# Boost.net
KiCad netlist of a schematic drawn in Altium Designer
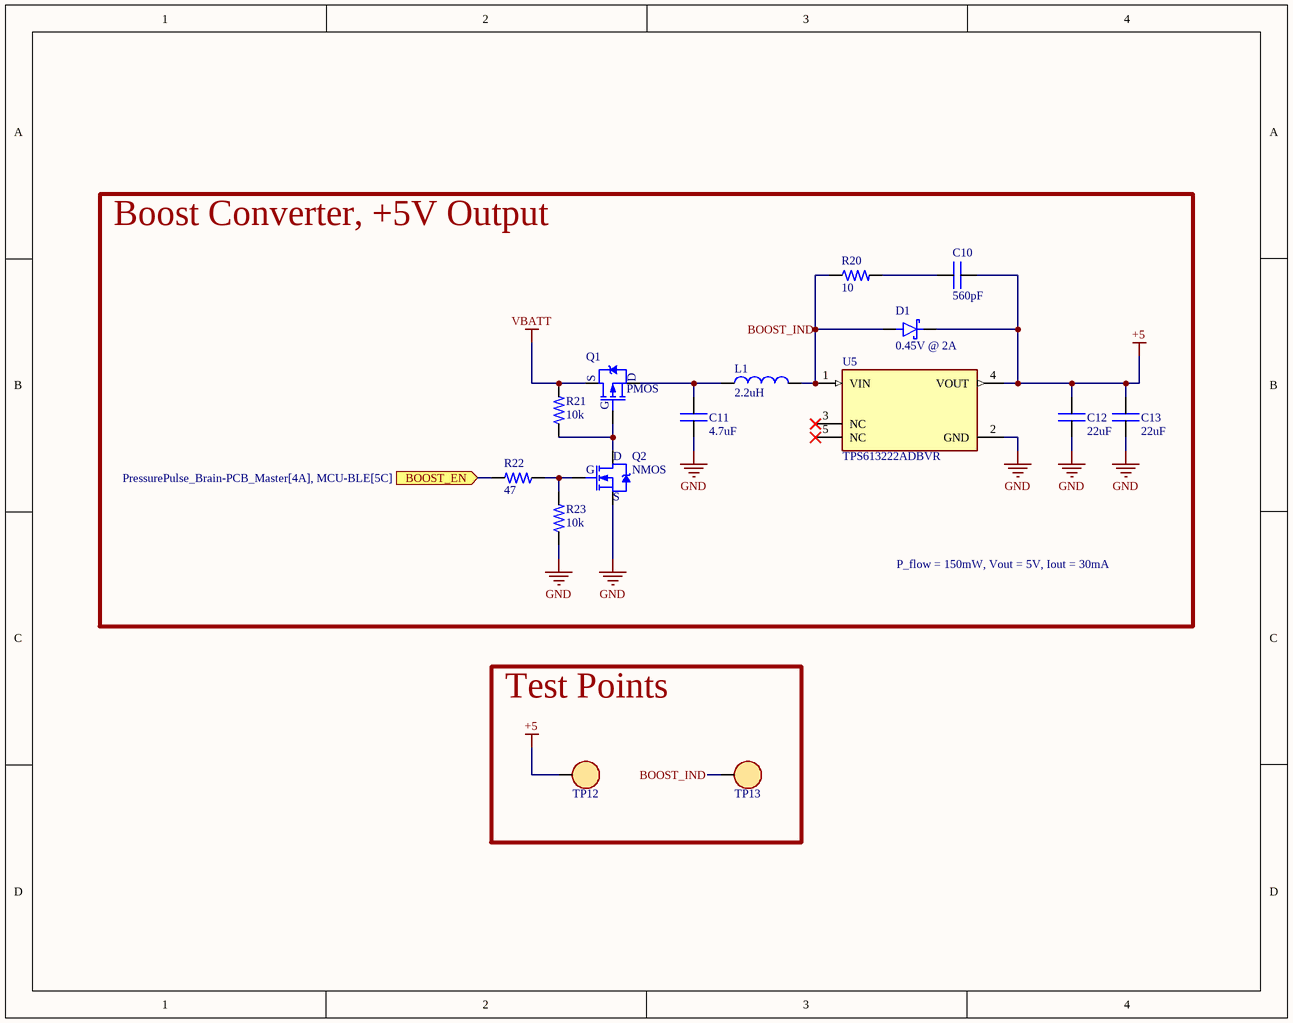
[diagram p0: Boost.SchDoc]

(export (version "E")
  (design (tool "Eeschema 10.0.6"))
  (components
    (comp (ref "C10")
      (value "560pF")
      (footprint "PressurePulse:0805C")
      (description "Capacitor")
      (fields (field (name "Comment") "CAP"))
      (libsource (lib "PressurePulse") (part "CAP"))
    )
    (comp (ref "C11")
      (value "4.7uF")
      (footprint "PressurePulse:0402C")
      (description "Capacitor")
      (fields (field (name "Comment") "CAP"))
      (libsource (lib "PressurePulse") (part "CAP"))
    )
    (comp (ref "C12")
      (value "22uF")
      (footprint "PressurePulse:0805C")
      (description "Capacitor")
      (fields (field (name "MFR") "Samsung Electro-Mechanics") (field (name "Comment") "CAP"))
      (libsource (lib "PressurePulse") (part "CAP"))
    )
    (comp (ref "C13")
      (value "22uF")
      (footprint "PressurePulse:0805C")
      (description "Capacitor")
      (fields (field (name "MFR") "Samsung Electro-Mechanics") (field (name "Comment") "CAP"))
      (libsource (lib "PressurePulse") (part "CAP"))
    )
    (comp (ref "D1")
      (value "0.45V @ 2A")
      (footprint "PressurePulse:SMAF")
      (fields (field (name "MFR") "Shandong Jingdao Microelectronics"))
      (libsource (lib "PressurePulse") (part "SCHOTTKY DIODE"))
    )
    (comp (ref "L1")
      (value "2.2uH")
      (footprint "PressurePulse:0805L")
      (description "INDUCTOR")
      (fields (field (name "MFR") "Sunlord") (field (name "Comment") "IND"))
      (libsource (lib "PressurePulse") (part "IND"))
    )
    (comp (ref "Q1")
      (value "PMOS")
      (footprint "PressurePulse:SOT-23")
      (description "P-Channel MOSFET")
      (fields (field (name "MFR") "Diodes Incorporated"))
      (libsource (lib "PressurePulse") (part "PMOS"))
    )
    (comp (ref "Q2")
      (value "NMOS")
      (footprint "PressurePulse:SOT-23")
      (description "100V 1.6A 1.3W 220mΩ@10V,1.6A N Channel SOT-23  MOSFETs ROHS")
      (fields (field (name "MFR") "Infineon"))
      (libsource (lib "PressurePulse") (part "NMOS"))
    )
    (comp (ref "R20")
      (value "10")
      (footprint "PressurePulse:2512R")
      (description "Resistor")
      (fields (field (name "Comment") "RES"))
      (libsource (lib "PressurePulse") (part "RES"))
    )
    (comp (ref "R21")
      (value "10k")
      (footprint "PressurePulse:0402R")
      (description "Resistor")
      (fields (field (name "Comment") "RES"))
      (libsource (lib "PressurePulse") (part "RES"))
    )
    (comp (ref "R22")
      (value "47")
      (footprint "PressurePulse:0402R")
      (description "Resistor")
      (fields (field (name "Comment") "RES"))
      (libsource (lib "PressurePulse") (part "RES"))
    )
    (comp (ref "R23")
      (value "10k")
      (footprint "PressurePulse:0402R")
      (description "Resistor")
      (fields (field (name "Comment") "RES"))
      (libsource (lib "PressurePulse") (part "RES"))
    )
    (comp (ref "TP12")
      (value "RH-5019")
      (footprint "PressurePulse:TP - RH-5019")
      (fields (field (name "MFR") "ronghe"))
      (libsource (lib "PressurePulse") (part "TEST POINT"))
    )
    (comp (ref "TP13")
      (value "RH-5019")
      (footprint "PressurePulse:TP - RH-5019")
      (fields (field (name "MFR") "ronghe"))
      (libsource (lib "PressurePulse") (part "TEST POINT"))
    )
    (comp (ref "U5")
      (value "TPS613222ADBVR")
      (footprint "PressurePulse:SOT-23-5")
      (description "6-uA Quiescent Current, 1.8-A Switch Current Boost Converter 5-SOT-23 -40 to 85")
      (fields (field (name "MFR") "Texas Instruments"))
      (libsource (lib "PressurePulse") (part "BOOST 3.3V-5V FIXED"))
    )
  )
  (nets
    (net (code "1") (name "+5") (class "Default")
      (node (ref "C10") (pin "2") (pinfunction "2_2") (pintype "passive"))
      (node (ref "C12") (pin "2") (pinfunction "2_2") (pintype "passive"))
      (node (ref "C13") (pin "2") (pinfunction "2_2") (pintype "passive"))
      (node (ref "D1") (pin "K") (pinfunction "K_K") (pintype "passive"))
      (node (ref "TP12") (pin "1") (pinfunction "1_1") (pintype "passive"))
      (node (ref "U5") (pin "4") (pinfunction "VOUT_4") (pintype "output"))
    )
    (net (code "2") (name "/BOOST_EN") (class "Default")
      (node (ref "R22") (pin "2") (pinfunction "2_2") (pintype "passive"))
    )
    (net (code "3") (name "/BOOST_IND") (class "Default")
      (node (ref "D1") (pin "A") (pinfunction "A_A") (pintype "passive"))
      (node (ref "L1") (pin "2") (pinfunction "2_2") (pintype "passive"))
      (node (ref "R20") (pin "1") (pinfunction "1_1") (pintype "passive"))
      (node (ref "TP13") (pin "1") (pinfunction "1_1") (pintype "passive"))
      (node (ref "U5") (pin "1") (pinfunction "VIN_1") (pintype "input"))
    )
    (net (code "4") (name "GND") (class "Default")
      (node (ref "C11") (pin "1") (pinfunction "1_1") (pintype "passive"))
      (node (ref "C12") (pin "1") (pinfunction "1_1") (pintype "passive"))
      (node (ref "C13") (pin "1") (pinfunction "1_1") (pintype "passive"))
      (node (ref "Q2") (pin "S") (pinfunction "S_S") (pintype "passive"))
      (node (ref "R23") (pin "1") (pinfunction "1_1") (pintype "passive"))
      (node (ref "U5") (pin "2") (pinfunction "GND_2") (pintype "power_in"))
    )
    (net (code "5") (name "Net-(C10-Pad1)") (class "Default")
      (node (ref "C10") (pin "1") (pinfunction "1_1") (pintype "passive"))
      (node (ref "R20") (pin "2") (pinfunction "2_2") (pintype "passive"))
    )
    (net (code "6") (name "Net-(C11-Pad2)") (class "Default")
      (node (ref "C11") (pin "2") (pinfunction "2_2") (pintype "passive"))
      (node (ref "L1") (pin "1") (pinfunction "1_1") (pintype "passive"))
      (node (ref "Q1") (pin "D") (pinfunction "D_D") (pintype "passive"))
    )
    (net (code "7") (name "Net-(Q1-PadG)") (class "Default")
      (node (ref "Q1") (pin "G") (pinfunction "G_G") (pintype "passive"))
      (node (ref "Q2") (pin "D") (pinfunction "D_D") (pintype "passive"))
      (node (ref "R21") (pin "1") (pinfunction "1_1") (pintype "passive"))
    )
    (net (code "8") (name "Net-(Q2-PadG)") (class "Default")
      (node (ref "Q2") (pin "G") (pinfunction "G_G") (pintype "passive"))
      (node (ref "R22") (pin "1") (pinfunction "1_1") (pintype "passive"))
      (node (ref "R23") (pin "2") (pinfunction "2_2") (pintype "passive"))
    )
    (net (code "9") (name "VBATT") (class "Default")
      (node (ref "Q1") (pin "S") (pinfunction "S_S") (pintype "passive"))
      (node (ref "R21") (pin "2") (pinfunction "2_2") (pintype "passive"))
    )
    (net (code "10") (name "unconnected-(U5-NC-Pad3)") (class "Default")
      (node (ref "U5") (pin "3") (pinfunction "NC_3") (pintype "passive+no_connect"))
    )
    (net (code "11") (name "unconnected-(U5-NC-Pad5)") (class "Default")
      (node (ref "U5") (pin "5") (pinfunction "NC_5") (pintype "passive+no_connect"))
    )
  )
)
